# external.net
KiCad netlist of a schematic drawn in Altium Designer
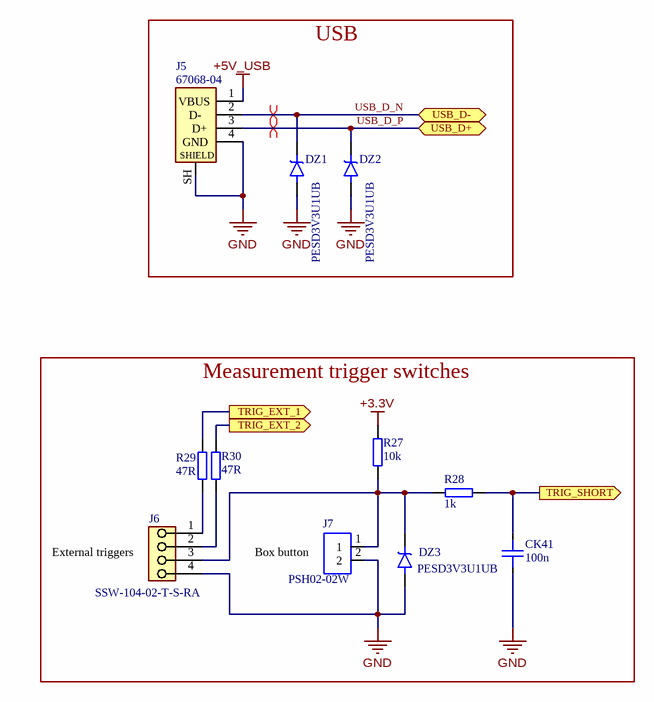
[diagram p0: external.SchDoc]

(export (version "E")
  (design (tool "Eeschema 10.0.6"))
  (components
    (comp (ref "CK41")
      (value "100n")
      (footprint "CAPC1608X09N(SMC0603)")
      (description "C; 100n; 50V; 10%; X7R; ??;")
      (fields
        (field (name "MANUFACTURER") "SAMSUNG EM: CL10B104KB8NNNC;;SAMSUNG EM: CL10B104KB8NNNO;;SAMSUNG EM: CL10B104KB8NNND")
      )
      (libsource (lib "altium_sql") (part "CK"))
    )
    (comp (ref "DZ1")
      (value "PESD3V3U1UB")
      (footprint "SODFL160X65-2N(SC79)")
      (description "CP; Voltage [V] - Unidirectional; 4.5; R:Yes; 1x;")
      (fields (field (name "MANUFACTURER") "Nexperia: PESD3V3U1UB,115;;NXP: PESD3V3U1UB,115"))
      (libsource (lib "altium_sql") (part "DTU"))
    )
    (comp (ref "DZ2")
      (value "PESD3V3U1UB")
      (footprint "SODFL160X65-2N(SC79)")
      (description "CP; Voltage [V] - Unidirectional; 4.5; R:Yes; 1x;")
      (fields (field (name "MANUFACTURER") "Nexperia: PESD3V3U1UB,115;;NXP: PESD3V3U1UB,115"))
      (libsource (lib "altium_sql") (part "DTU"))
    )
    (comp (ref "DZ3")
      (value "PESD3V3U1UB")
      (footprint "SODFL160X65-2N(SC79)")
      (description "CP; Voltage [V] - Unidirectional; 4.5; R:Yes; 1x;")
      (fields (field (name "MANUFACTURER") "Nexperia: PESD3V3U1UB,115;;NXP: PESD3V3U1UB,115"))
      (libsource (lib "altium_sql") (part "DTU"))
    )
    (comp (ref "J5")
      (value "67068-04")
      (footprint "USB-B")
      (description "Con; USB; 1x; PCB; Right angle; 250V; 1.5A; Female; Gold; ??;")
      (fields (field (name "MANUFACTURER") "HSUAN MAO: C8317-04BFHSB0R;;HSM: C8317-04BFHSB0R"))
      (libsource (lib "altium_sql") (part "EJ_USB1"))
    )
    (comp (ref "J6")
      (value "SSW-104-02-T-S-RA")
      (footprint "SSW-104-02-T-S-RA")
      (description "Female Header, Single row, 1 x 4, R/A, THT")
      (libsource (lib "custom-footprints") (part "SSW-104-02-T-S-RA"))
    )
    (comp (ref "J7")
      (value "PSH02-02W")
      (footprint "Official_PSH0202W")
      (description "Con; PFH/PSH; 2x; PCB; Right angle; 250V; 3A; Male; Tin; ??;")
      (fields (field (name "MANUFACTURER") "Neltron: 2217R-XX-WH2"))
      (libsource (lib "altium_sql") (part "EJ-PSH0202WXX0"))
    )
    (comp (ref "R27")
      (value "10k")
      (footprint "RESC2012X06N(SMR0805)")
      (description "R; 10k; 0.125W; 1%; 150V; Thick Film; ±100ppm/K; 1x;")
      (libsource (lib "altium_sql") (part "R"))
    )
    (comp (ref "R28")
      (value "1k")
      (footprint "RESC2012X06N(SMR0805)")
      (description "R; 1k; 0.125W; 1%; 150V; Thick Film; ±100ppm/K; 1x;")
      (libsource (lib "altium_sql") (part "R"))
    )
    (comp (ref "R29")
      (value "47R")
      (footprint "RESC2012X06N(SMR0805)")
      (description "R; 47R; 0.125W; 1%; 150V; Thick Film; ±100ppm/K; 1x;")
      (libsource (lib "altium_sql") (part "R"))
    )
    (comp (ref "R30")
      (value "47R")
      (footprint "RESC2012X06N(SMR0805)")
      (description "R; 47R; 0.125W; 1%; 150V; Thick Film; ±100ppm/K; 1x;")
      (libsource (lib "altium_sql") (part "R"))
    )
  )
  (nets
    (net (code "1") (name "+3.3V") (class "Default")
      (node (ref "R27") (pin "2") (pinfunction "2_2") (pintype "passive"))
    )
    (net (code "2") (name "+5V_USB") (class "Default")
      (node (ref "J5") (pin "1") (pinfunction "VBUS_1") (pintype "passive"))
    )
    (net (code "3") (name "/TRIG_EXT_1") (class "Default")
      (node (ref "R29") (pin "2") (pinfunction "2_2") (pintype "passive"))
    )
    (net (code "4") (name "/TRIG_EXT_2") (class "Default")
      (node (ref "R30") (pin "2") (pinfunction "2_2") (pintype "passive"))
    )
    (net (code "5") (name "/TRIG_SHORT") (class "Default")
      (node (ref "CK41") (pin "1") (pinfunction "1_1") (pintype "passive"))
      (node (ref "R28") (pin "1") (pinfunction "1_1") (pintype "passive"))
    )
    (net (code "6") (name "/USB_D_N") (class "Default")
      (node (ref "DZ1") (pin "1") (pinfunction "C_1") (pintype "passive"))
      (node (ref "J5") (pin "2") (pinfunction "D-_2") (pintype "passive"))
    )
    (net (code "7") (name "/USB_D_P") (class "Default")
      (node (ref "DZ2") (pin "1") (pinfunction "C_1") (pintype "passive"))
      (node (ref "J5") (pin "3") (pinfunction "D+_3") (pintype "passive"))
    )
    (net (code "8") (name "GND") (class "Default")
      (node (ref "CK41") (pin "2") (pinfunction "2_2") (pintype "passive"))
      (node (ref "DZ1") (pin "2") (pinfunction "A_2") (pintype "passive"))
      (node (ref "DZ2") (pin "2") (pinfunction "A_2") (pintype "passive"))
      (node (ref "DZ3") (pin "2") (pinfunction "A_2") (pintype "passive"))
      (node (ref "J5") (pin "4") (pinfunction "GND_4") (pintype "passive"))
      (node (ref "J5") (pin "SH") (pinfunction "SHIELD_SH") (pintype "passive"))
      (node (ref "J6") (pin "4") (pinfunction "4_4") (pintype "passive"))
      (node (ref "J7") (pin "2") (pinfunction "2_2") (pintype "passive"))
    )
    (net (code "9") (name "Net-(DZ3-C)") (class "Default")
      (node (ref "DZ3") (pin "1") (pinfunction "C_1") (pintype "passive"))
      (node (ref "J6") (pin "3") (pinfunction "3_3") (pintype "passive"))
      (node (ref "J7") (pin "1") (pinfunction "1_1") (pintype "passive"))
      (node (ref "R27") (pin "1") (pinfunction "1_1") (pintype "passive"))
      (node (ref "R28") (pin "2") (pinfunction "2_2") (pintype "passive"))
    )
    (net (code "10") (name "Net-(J6-Pad1)") (class "Default")
      (node (ref "J6") (pin "1") (pinfunction "1_1") (pintype "passive"))
      (node (ref "R29") (pin "1") (pinfunction "1_1") (pintype "passive"))
    )
    (net (code "11") (name "Net-(J6-Pad2)") (class "Default")
      (node (ref "J6") (pin "2") (pinfunction "2_2") (pintype "passive"))
      (node (ref "R30") (pin "1") (pinfunction "1_1") (pintype "passive"))
    )
  )
)
